# design.net
KiCad netlist of a schematic drawn in Altium Designer
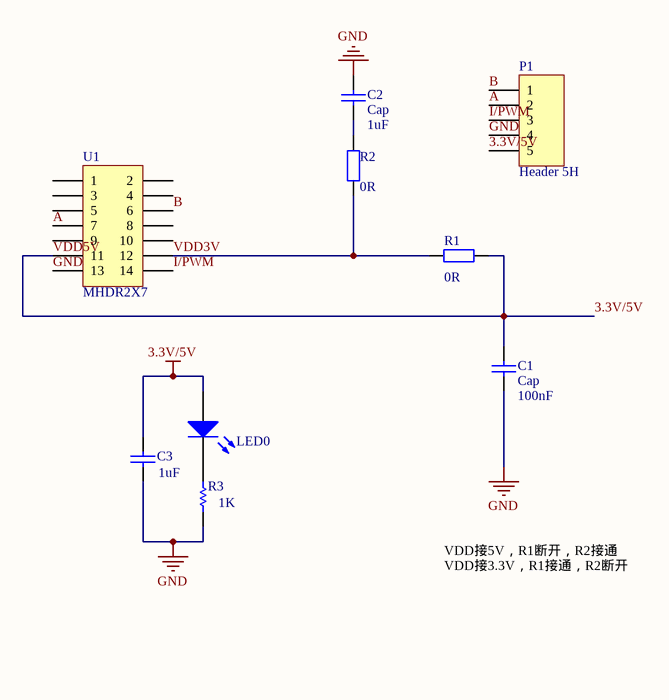
[diagram p0: 芯片.SchDoc]

(export (version "E")
  (design (tool "Eeschema 10.0.6"))
  (components
    (comp (ref "C1")
      (value "Cap")
      (footprint "0805")
      (description "Capacitor")
      (fields (field (name "ALTIUM_VALUE") "100nF") (field (name "PUBLISHER") "Altium Limited"))
      (libsource (lib "Miscellaneous Devices") (part "Cap"))
    )
    (comp (ref "C2")
      (value "Cap")
      (footprint "0805")
      (description "Capacitor")
      (fields (field (name "ALTIUM_VALUE") "1uF") (field (name "PUBLISHER") "Altium Limited"))
      (libsource (lib "Miscellaneous Devices") (part "Cap"))
    )
    (comp (ref "C3")
      (value "1uF")
      (footprint "0805")
      (description "Capacitor")
      (fields (field (name "Comment") "Cap") (field (name "PUBLISHER") "Altium Limited"))
      (libsource (lib "Miscellaneous Devices") (part "Cap"))
    )
    (comp (ref "D1")
      (value "LED0")
      (footprint "0805")
      (description "Typical INFRARED GaAs LED")
      (fields (field (name "PUBLISHER") "Altium Limited"))
      (libsource (lib "Miscellaneous Devices") (part "LED0"))
    )
    (comp (ref "P1")
      (value "Header 5H")
      (footprint "5pin_XH2.54")
      (description "Header, 5-Pin, Right Angle")
      (fields (field (name "PUBLISHER") "Altium Limited"))
      (libsource (lib "Miscellaneous Connectors") (part "Header 5H"))
    )
    (comp (ref "R1")
      (value "0R")
      (footprint "0805")
      (description "Resistor")
      (fields (field (name "Comment") "Res2") (field (name "PUBLISHER") "Altium Limited"))
      (libsource (lib "") (part "Res2_1"))
    )
    (comp (ref "R2")
      (value "0R")
      (footprint "0805")
      (description "Resistor")
      (fields (field (name "Comment") "Res2") (field (name "PUBLISHER") "Altium Limited"))
      (libsource (lib "Miscellaneous Devices") (part "Res2"))
    )
    (comp (ref "R3")
      (value "1K")
      (footprint "0805")
      (description "Resistor")
      (fields (field (name "Comment") "Res1") (field (name "PUBLISHER") "Altium Limited"))
      (libsource (lib "Miscellaneous Devices") (part "Res1"))
    )
    (comp (ref "U1")
      (value "MHDR2X7")
      (footprint "SSOP14")
      (description "Header, 7-Pin, Dual row")
      (fields (field (name "PUBLISHER") "Altium Limited"))
      (libsource (lib "Miscellaneous Connectors") (part "MHDR2X7"))
    )
  )
  (nets
    (net (code "1") (name "/A") (class "Default")
      (node (ref "P1") (pin "2") (pinfunction "2_2") (pintype "passive"))
      (node (ref "U1") (pin "7") (pinfunction "7_7") (pintype "passive"))
    )
    (net (code "2") (name "/B") (class "Default")
      (node (ref "P1") (pin "1") (pinfunction "1_1") (pintype "passive"))
      (node (ref "U1") (pin "6") (pinfunction "6_6") (pintype "passive"))
    )
    (net (code "3") (name "/I{slash}PWM") (class "Default")
      (node (ref "P1") (pin "3") (pinfunction "3_3") (pintype "passive"))
      (node (ref "U1") (pin "14") (pinfunction "14_14") (pintype "passive"))
    )
    (net (code "4") (name "/VDD3V") (class "Default")
      (node (ref "R1") (pin "1") (pinfunction "1_1") (pintype "passive"))
      (node (ref "R2") (pin "1") (pinfunction "1_1") (pintype "passive"))
      (node (ref "U1") (pin "12") (pinfunction "12_12") (pintype "passive"))
    )
    (net (code "5") (name "3.3V{slash}5V") (class "Default")
      (node (ref "C1") (pin "1") (pinfunction "1_1") (pintype "passive"))
      (node (ref "C3") (pin "2") (pinfunction "2_2") (pintype "passive"))
      (node (ref "D1") (pin "1") (pinfunction "A_1") (pintype "passive"))
      (node (ref "P1") (pin "5") (pinfunction "5_5") (pintype "passive"))
      (node (ref "R1") (pin "2") (pinfunction "2_2") (pintype "passive"))
      (node (ref "U1") (pin "11") (pinfunction "11_11") (pintype "passive"))
    )
    (net (code "6") (name "GND") (class "Default")
      (node (ref "C1") (pin "2") (pinfunction "2_2") (pintype "passive"))
      (node (ref "C2") (pin "1") (pinfunction "1_1") (pintype "passive"))
      (node (ref "C3") (pin "1") (pinfunction "1_1") (pintype "passive"))
      (node (ref "P1") (pin "4") (pinfunction "4_4") (pintype "passive"))
      (node (ref "R3") (pin "1") (pinfunction "1_1") (pintype "passive"))
      (node (ref "U1") (pin "13") (pinfunction "13_13") (pintype "passive"))
    )
    (net (code "7") (name "Net-(C2-Pad2)") (class "Default")
      (node (ref "C2") (pin "2") (pinfunction "2_2") (pintype "passive"))
      (node (ref "R2") (pin "2") (pinfunction "2_2") (pintype "passive"))
    )
    (net (code "8") (name "Net-(D1-K)") (class "Default")
      (node (ref "D1") (pin "2") (pinfunction "K_2") (pintype "passive"))
      (node (ref "R3") (pin "2") (pinfunction "2_2") (pintype "passive"))
    )
    (net (code "9") (name "unconnected-(U1-Pad1)") (class "Default")
      (node (ref "U1") (pin "1") (pinfunction "1_1") (pintype "passive"))
    )
    (net (code "10") (name "unconnected-(U1-Pad2)") (class "Default")
      (node (ref "U1") (pin "2") (pinfunction "2_2") (pintype "passive"))
    )
    (net (code "11") (name "unconnected-(U1-Pad3)") (class "Default")
      (node (ref "U1") (pin "3") (pinfunction "3_3") (pintype "passive"))
    )
    (net (code "12") (name "unconnected-(U1-Pad4)") (class "Default")
      (node (ref "U1") (pin "4") (pinfunction "4_4") (pintype "passive"))
    )
    (net (code "13") (name "unconnected-(U1-Pad5)") (class "Default")
      (node (ref "U1") (pin "5") (pinfunction "5_5") (pintype "passive"))
    )
    (net (code "14") (name "unconnected-(U1-Pad8)") (class "Default")
      (node (ref "U1") (pin "8") (pinfunction "8_8") (pintype "passive"))
    )
    (net (code "15") (name "unconnected-(U1-Pad9)") (class "Default")
      (node (ref "U1") (pin "9") (pinfunction "9_9") (pintype "passive"))
    )
    (net (code "16") (name "unconnected-(U1-Pad10)") (class "Default")
      (node (ref "U1") (pin "10") (pinfunction "10_10") (pintype "passive"))
    )
  )
)
